# LF_Sensor_Board.net
KiCad netlist of a schematic drawn in Altium Designer
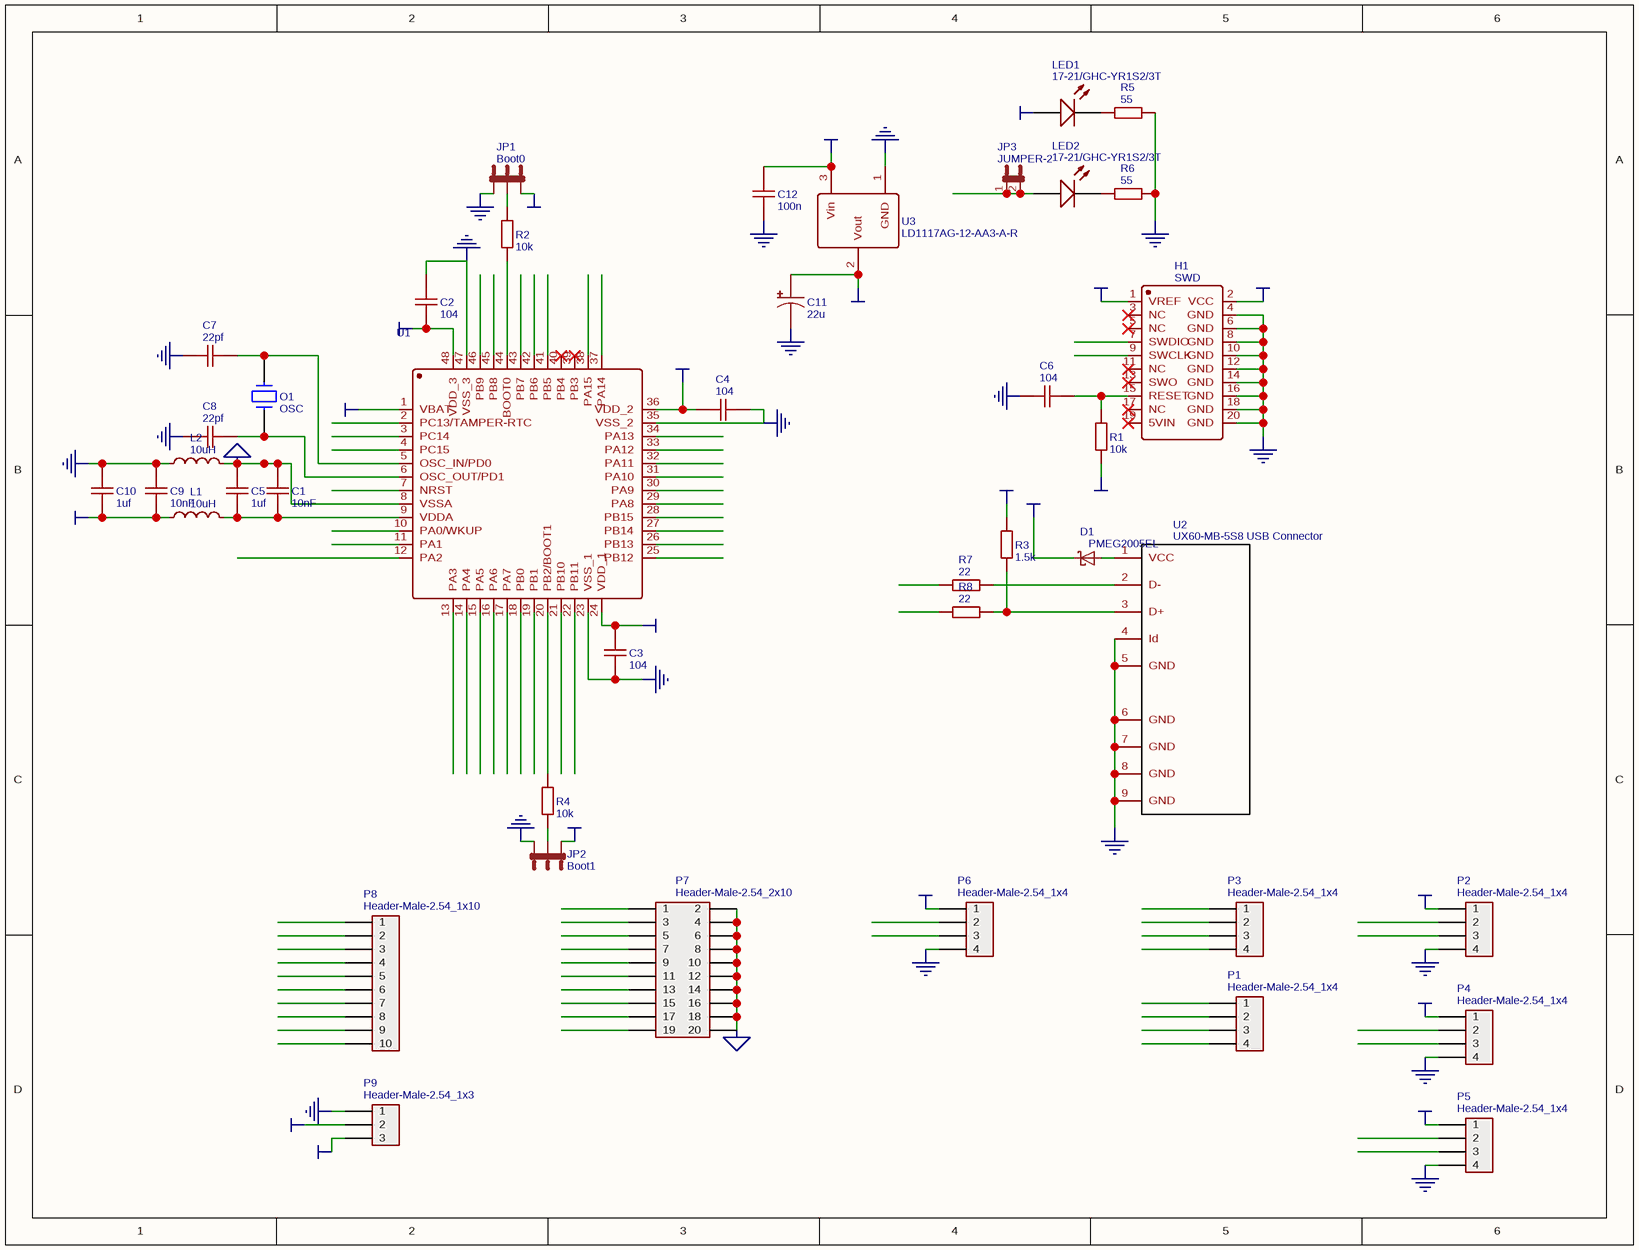
[diagram p0: LF_Sensor_Board.schdoc]

(export (version "E")
  (design (tool "Eeschema 10.0.6"))
  (components
    (comp (ref "C1")
      (value "10nF")
      (fields (field (name "BOM_MANUFACTURER PART") "?"))
      (libsource (lib "altium-import") (part "root_1_10nF_"))
    )
    (comp (ref "C2")
      (value "104")
      (fields (field (name "BOM_MANUFACTURER PART") "?"))
      (libsource (lib "altium-import") (part "root_1_104_"))
    )
    (comp (ref "C3")
      (value "104")
      (fields (field (name "BOM_MANUFACTURER PART") "?"))
      (libsource (lib "altium-import") (part "root_1_104_"))
    )
    (comp (ref "C4")
      (value "104")
      (fields (field (name "BOM_MANUFACTURER PART") "?"))
      (libsource (lib "altium-import") (part "root_0_104_"))
    )
    (comp (ref "C5")
      (value "1uf")
      (fields (field (name "BOM_MANUFACTURER PART") "?"))
      (libsource (lib "altium-import") (part "root_1_1uf_"))
    )
    (comp (ref "C6")
      (value "104")
      (fields (field (name "BOM_MANUFACTURER PART") "?"))
      (libsource (lib "altium-import") (part "root_2_104_"))
    )
    (comp (ref "C7")
      (value "22pf")
      (fields (field (name "BOM_MANUFACTURER PART") "?"))
      (libsource (lib "altium-import") (part "root_0_22pf_"))
    )
    (comp (ref "C8")
      (value "22pf")
      (fields (field (name "BOM_MANUFACTURER PART") "?"))
      (libsource (lib "altium-import") (part "root_0_22pf_"))
    )
    (comp (ref "C9")
      (value "10nF")
      (fields (field (name "BOM_MANUFACTURER PART") "?"))
      (libsource (lib "altium-import") (part "root_1_10nF_"))
    )
    (comp (ref "C10")
      (value "1uf")
      (fields (field (name "BOM_MANUFACTURER PART") "?"))
      (libsource (lib "altium-import") (part "root_1_1uf_"))
    )
    (comp (ref "C11")
      (value "22u")
      (fields (field (name "BOM_MANUFACTURER PART") "?"))
      (libsource (lib "altium-import") (part "root_0_22u_"))
    )
    (comp (ref "C12")
      (value "100n")
      (fields (field (name "BOM_MANUFACTURER PART") "?"))
      (libsource (lib "altium-import") (part "root_1_100n_"))
    )
    (comp (ref "D1")
      (value "PMEG2005EL")
      (fields (field (name "BOM_MANUFACTURER PART") "?"))
      (libsource (lib "altium-import") (part "root_0_PMEG2005EL_"))
    )
    (comp (ref "H1")
      (value "SWD")
      (fields (field (name "BOM_MANUFACTURER PART") "?"))
      (libsource (lib "altium-import") (part "root_0_SWD_"))
    )
    (comp (ref "JP1")
      (value "Boot0")
      (fields (field (name "BOM_MANUFACTURER PART") "?") (field (name "CONTRIBUTOR") "SparkFun"))
      (libsource (lib "altium-import") (part "root_0_Boot0_"))
    )
    (comp (ref "JP2")
      (value "Boot1")
      (fields (field (name "BOM_MANUFACTURER PART") "?") (field (name "CONTRIBUTOR") "SparkFun"))
      (libsource (lib "altium-import") (part "root_0_Boot1_"))
    )
    (comp (ref "JP3")
      (value "JUMPER-2")
      (fields (field (name "BOM_MANUFACTURER PART") "?") (field (name "CONTRIBUTOR") "SparkFun"))
      (libsource (lib "altium-import") (part "root_0_JUMPER-2_"))
    )
    (comp (ref "L1")
      (value "10uH")
      (fields (field (name "BOM_MANUFACTURER PART") "?"))
      (libsource (lib "altium-import") (part "root_0_10uH_"))
    )
    (comp (ref "L2")
      (value "10uH")
      (fields (field (name "BOM_MANUFACTURER PART") "?"))
      (libsource (lib "altium-import") (part "root_0_10uH_"))
    )
    (comp (ref "LED1")
      (value "17-21/GHC-YR1S2/3T")
      (fields (field (name "BOM_SUPPLIER PART") "E73546"))
      (libsource (lib "altium-import") (part "root_0_17-21/GHC-YR1S2/3T_"))
    )
    (comp (ref "LED2")
      (value "17-21/GHC-YR1S2/3T")
      (fields (field (name "BOM_SUPPLIER PART") "E73546"))
      (libsource (lib "altium-import") (part "root_0_17-21/GHC-YR1S2/3T_"))
    )
    (comp (ref "O1")
      (value "OSC")
      (description "晶振")
      (fields (field (name "BOM_MANUFACTURER PART") "?"))
      (libsource (lib "altium-import") (part "root_0_OSC_"))
    )
    (comp (ref "P1")
      (value "Header-Male-2.54_1x4")
      (fields (field (name "BOM_SUPPLIER PART") "E59481"))
      (libsource (lib "altium-import") (part "root_0_Header-Male-2.54_1x4_"))
    )
    (comp (ref "P2")
      (value "Header-Male-2.54_1x4")
      (fields (field (name "BOM_SUPPLIER PART") "E59481"))
      (libsource (lib "altium-import") (part "root_0_Header-Male-2.54_1x4_"))
    )
    (comp (ref "P3")
      (value "Header-Male-2.54_1x4")
      (fields (field (name "BOM_SUPPLIER PART") "E59481"))
      (libsource (lib "altium-import") (part "root_0_Header-Male-2.54_1x4_"))
    )
    (comp (ref "P4")
      (value "Header-Male-2.54_1x4")
      (fields (field (name "BOM_SUPPLIER PART") "E59481"))
      (libsource (lib "altium-import") (part "root_0_Header-Male-2.54_1x4_"))
    )
    (comp (ref "P5")
      (value "Header-Male-2.54_1x4")
      (fields (field (name "BOM_SUPPLIER PART") "E59481"))
      (libsource (lib "altium-import") (part "root_0_Header-Male-2.54_1x4_"))
    )
    (comp (ref "P6")
      (value "Header-Male-2.54_1x4")
      (fields (field (name "BOM_SUPPLIER PART") "E59481"))
      (libsource (lib "altium-import") (part "root_0_Header-Male-2.54_1x4_"))
    )
    (comp (ref "P7")
      (value "Header-Male-2.54_2x10")
      (fields (field (name "BOM_SUPPLIER PART") "E62032"))
      (libsource (lib "altium-import") (part "root_0_Header-Male-2.54_2x10_"))
    )
    (comp (ref "P8")
      (value "Header-Male-2.54_1x10")
      (fields (field (name "BOM_SUPPLIER PART") "E57369"))
      (libsource (lib "altium-import") (part "root_0_Header-Male-2.54_1x10_"))
    )
    (comp (ref "P9")
      (value "Header-Male-2.54_1x3")
      (fields (field (name "BOM_SUPPLIER PART") "E49257"))
      (libsource (lib "altium-import") (part "root_0_Header-Male-2.54_1x3_"))
    )
    (comp (ref "R1")
      (value "10k")
      (fields (field (name "BOM_MANUFACTURER PART") "?"))
      (libsource (lib "altium-import") (part "root_1_10k_"))
    )
    (comp (ref "R2")
      (value "10k")
      (fields (field (name "BOM_MANUFACTURER PART") "?"))
      (libsource (lib "altium-import") (part "root_1_10k_"))
    )
    (comp (ref "R3")
      (value "1.5k")
      (fields (field (name "BOM_MANUFACTURER PART") "?"))
      (libsource (lib "altium-import") (part "root_1_1.5k_"))
    )
    (comp (ref "R4")
      (value "10k")
      (fields (field (name "BOM_MANUFACTURER PART") "?"))
      (libsource (lib "") (part "root_1_10k__1"))
    )
    (comp (ref "R5")
      (value "55")
      (fields (field (name "BOM_MANUFACTURER PART") "?"))
      (libsource (lib "altium-import") (part "root_0_55_"))
    )
    (comp (ref "R6")
      (value "55")
      (fields (field (name "BOM_MANUFACTURER PART") "?"))
      (libsource (lib "altium-import") (part "root_0_55_"))
    )
    (comp (ref "R7")
      (value "22")
      (fields (field (name "BOM_MANUFACTURER PART") "?"))
      (libsource (lib "altium-import") (part "root_0_22_"))
    )
    (comp (ref "R8")
      (value "22")
      (fields (field (name "BOM_MANUFACTURER PART") "?"))
      (libsource (lib "altium-import") (part "root_0_22_"))
    )
    (comp (ref "U1")
      (value "STM32F103C8T6")
      (fields (field (name "BOM_MANUFACTURER PART") "?"))
      (libsource (lib "altium-import") (part "root_0_STM32F103C8T6_"))
    )
    (comp (ref "U2")
      (value "UX60-MB-5S8 USB Connector")
      (fields (field (name "BOM_MANUFACTURER PART") "?") (field (name "CONTRIBUTOR") "fbruckm"))
      (libsource (lib "altium-import") (part "root_2_UX60-MB-5S8 USB Connector_"))
    )
    (comp (ref "U3")
      (value "LD1117AG-12-AA3-A-R")
      (fields (field (name "BOM_SUPPLIER PART") "E75486"))
      (libsource (lib "altium-import") (part "root_1_LD1117AG-12-AA3-A-R_"))
    )
  )
  (nets
    (net (code "1") (name "<NO NET>") (class "Default")
      (node (ref "C1") (pin "2") (pinfunction "2_2") (pintype "passive"))
      (node (ref "C10") (pin "1") (pinfunction "1_1") (pintype "passive"))
      (node (ref "C10") (pin "2") (pinfunction "2_2") (pintype "passive"))
      (node (ref "C11") (pin "1") (pinfunction "1_1") (pintype "passive"))
      (node (ref "C11") (pin "2") (pinfunction "2_2") (pintype "passive"))
      (node (ref "C12") (pin "1") (pinfunction "1_1") (pintype "passive"))
      (node (ref "C12") (pin "2") (pinfunction "2_2") (pintype "passive"))
      (node (ref "C2") (pin "1") (pinfunction "1_1") (pintype "passive"))
      (node (ref "C2") (pin "2") (pinfunction "2_2") (pintype "passive"))
      (node (ref "C3") (pin "1") (pinfunction "1_1") (pintype "passive"))
      (node (ref "C3") (pin "2") (pinfunction "2_2") (pintype "passive"))
      (node (ref "C4") (pin "1") (pinfunction "1_1") (pintype "passive"))
      (node (ref "C4") (pin "2") (pinfunction "2_2") (pintype "passive"))
      (node (ref "C5") (pin "2") (pinfunction "2_2") (pintype "passive"))
      (node (ref "C6") (pin "2") (pinfunction "2_2") (pintype "passive"))
      (node (ref "C7") (pin "1") (pinfunction "1_1") (pintype "passive"))
      (node (ref "C8") (pin "1") (pinfunction "1_1") (pintype "passive"))
      (node (ref "C9") (pin "1") (pinfunction "1_1") (pintype "passive"))
      (node (ref "C9") (pin "2") (pinfunction "2_2") (pintype "passive"))
      (node (ref "D1") (pin "1") (pinfunction "K_1") (pintype "passive"))
      (node (ref "H1") (pin "1") (pinfunction "VREF_1") (pintype "passive"))
      (node (ref "H1") (pin "10") (pinfunction "GND_10") (pintype "passive"))
      (node (ref "H1") (pin "12") (pinfunction "GND_12") (pintype "passive"))
      (node (ref "H1") (pin "14") (pinfunction "GND_14") (pintype "passive"))
      (node (ref "H1") (pin "16") (pinfunction "GND_16") (pintype "passive"))
      (node (ref "H1") (pin "18") (pinfunction "GND_18") (pintype "passive"))
      (node (ref "H1") (pin "2") (pinfunction "VCC_2") (pintype "passive"))
      (node (ref "H1") (pin "20") (pinfunction "GND_20") (pintype "passive"))
      (node (ref "H1") (pin "4") (pinfunction "GND_4") (pintype "passive"))
      (node (ref "H1") (pin "6") (pinfunction "GND_6") (pintype "passive"))
      (node (ref "H1") (pin "8") (pinfunction "GND_8") (pintype "passive"))
      (node (ref "JP1") (pin "1") (pinfunction "1_1") (pintype "passive"))
      (node (ref "JP1") (pin "3") (pinfunction "3_3") (pintype "passive"))
      (node (ref "JP2") (pin "1") (pinfunction "1_1") (pintype "passive"))
      (node (ref "JP2") (pin "3") (pinfunction "3_3") (pintype "passive"))
      (node (ref "L1") (pin "1") (pinfunction "1_1") (pintype "passive"))
      (node (ref "L2") (pin "1") (pinfunction "1_1") (pintype "passive"))
      (node (ref "L2") (pin "2") (pinfunction "2_2") (pintype "passive"))
      (node (ref "LED1") (pin "1") (pinfunction "A_1") (pintype "passive"))
      (node (ref "P2") (pin "1") (pinfunction "1_1") (pintype "passive"))
      (node (ref "P2") (pin "4") (pinfunction "4_4") (pintype "passive"))
      (node (ref "P4") (pin "1") (pinfunction "1_1") (pintype "passive"))
      (node (ref "P4") (pin "4") (pinfunction "4_4") (pintype "passive"))
      (node (ref "P5") (pin "1") (pinfunction "1_1") (pintype "passive"))
      (node (ref "P5") (pin "4") (pinfunction "4_4") (pintype "passive"))
      (node (ref "P6") (pin "1") (pinfunction "1_1") (pintype "passive"))
      (node (ref "P6") (pin "4") (pinfunction "4_4") (pintype "passive"))
      (node (ref "P7") (pin "10") (pinfunction "10_10") (pintype "passive"))
      (node (ref "P7") (pin "12") (pinfunction "12_12") (pintype "passive"))
      (node (ref "P7") (pin "14") (pinfunction "14_14") (pintype "passive"))
      (node (ref "P7") (pin "16") (pinfunction "16_16") (pintype "passive"))
      (node (ref "P7") (pin "18") (pinfunction "18_18") (pintype "passive"))
      (node (ref "P7") (pin "2") (pinfunction "2_2") (pintype "passive"))
      (node (ref "P7") (pin "20") (pinfunction "20_20") (pintype "passive"))
      (node (ref "P7") (pin "4") (pinfunction "4_4") (pintype "passive"))
      (node (ref "P7") (pin "6") (pinfunction "6_6") (pintype "passive"))
      (node (ref "P7") (pin "8") (pinfunction "8_8") (pintype "passive"))
      (node (ref "P9") (pin "1") (pinfunction "1_1") (pintype "passive"))
      (node (ref "P9") (pin "2") (pinfunction "2_2") (pintype "passive"))
      (node (ref "P9") (pin "3") (pinfunction "3_3") (pintype "passive"))
      (node (ref "R1") (pin "1") (pinfunction "1_1") (pintype "passive"))
      (node (ref "R3") (pin "2") (pinfunction "2_2") (pintype "passive"))
      (node (ref "R5") (pin "2") (pinfunction "2_2") (pintype "passive"))
      (node (ref "R6") (pin "2") (pinfunction "2_2") (pintype "passive"))
      (node (ref "U1") (pin "1") (pinfunction "VBAT_1") (pintype "passive"))
      (node (ref "U1") (pin "23") (pinfunction "VSS_1_23") (pintype "passive"))
      (node (ref "U1") (pin "24") (pinfunction "VDD_1_24") (pintype "passive"))
      (node (ref "U1") (pin "35") (pinfunction "VSS_2_35") (pintype "passive"))
      (node (ref "U1") (pin "36") (pinfunction "VDD_2_36") (pintype "passive"))
      (node (ref "U1") (pin "47") (pinfunction "VSS_3_47") (pintype "passive"))
      (node (ref "U1") (pin "48") (pinfunction "VDD_3_48") (pintype "passive"))
      (node (ref "U1") (pin "8") (pinfunction "VSSA_8") (pintype "passive"))
      (node (ref "U2") (pin "4") (pinfunction "Id_4") (pintype "passive"))
      (node (ref "U2") (pin "5") (pinfunction "GND_5") (pintype "passive"))
      (node (ref "U2") (pin "6") (pinfunction "GND_6") (pintype "passive"))
      (node (ref "U2") (pin "7") (pinfunction "GND_7") (pintype "passive"))
      (node (ref "U2") (pin "8") (pinfunction "GND_8") (pintype "passive"))
      (node (ref "U2") (pin "9") (pinfunction "GND_9") (pintype "passive"))
      (node (ref "U3") (pin "1") (pinfunction "GND_1") (pintype "passive"))
      (node (ref "U3") (pin "2") (pinfunction "Vout_2") (pintype "passive"))
      (node (ref "U3") (pin "3") (pinfunction "Vin_3") (pintype "passive"))
    )
    (net (code "2") (name "Net-(D1-A)") (class "Default")
      (node (ref "D1") (pin "2") (pinfunction "A_2") (pintype "passive"))
      (node (ref "U2") (pin "1") (pinfunction "VCC_1") (pintype "passive"))
    )
    (net (code "3") (name "Net-(H1-RESET)") (class "Default")
      (node (ref "C6") (pin "1") (pinfunction "1_1") (pintype "passive"))
      (node (ref "H1") (pin "15") (pinfunction "RESET_15") (pintype "passive"))
      (node (ref "R1") (pin "2") (pinfunction "2_2") (pintype "passive"))
    )
    (net (code "4") (name "Net-(JP1-Pad2)") (class "Default")
      (node (ref "JP1") (pin "2") (pinfunction "2_2") (pintype "passive"))
      (node (ref "R2") (pin "2") (pinfunction "2_2") (pintype "passive"))
    )
    (net (code "5") (name "Net-(JP2-Pad2)") (class "Default")
      (node (ref "JP2") (pin "2") (pinfunction "2_2") (pintype "passive"))
      (node (ref "R4") (pin "2") (pinfunction "2_2") (pintype "passive"))
    )
    (net (code "6") (name "Net-(LED1-C)") (class "Default")
      (node (ref "LED1") (pin "2") (pinfunction "C_2") (pintype "passive"))
      (node (ref "R5") (pin "1") (pinfunction "1_1") (pintype "passive"))
    )
    (net (code "7") (name "Net-(LED2-A)") (class "Default")
      (node (ref "JP3") (pin "1") (pinfunction "1_1") (pintype "passive"))
      (node (ref "JP3") (pin "2") (pinfunction "2_2") (pintype "passive"))
      (node (ref "LED2") (pin "1") (pinfunction "A_1") (pintype "passive"))
    )
    (net (code "8") (name "Net-(LED2-C)") (class "Default")
      (node (ref "LED2") (pin "2") (pinfunction "C_2") (pintype "passive"))
      (node (ref "R6") (pin "1") (pinfunction "1_1") (pintype "passive"))
    )
    (net (code "9") (name "Net-(U1-BOOT0)") (class "Default")
      (node (ref "R2") (pin "1") (pinfunction "1_1") (pintype "passive"))
      (node (ref "U1") (pin "44") (pinfunction "BOOT0_44") (pintype "passive"))
    )
    (net (code "10") (name "Net-(U1-OSC_IN{slash}PD0)") (class "Default")
      (node (ref "C7") (pin "2") (pinfunction "2_2") (pintype "passive"))
      (node (ref "O1") (pin "2") (pinfunction "2_2") (pintype "passive"))
      (node (ref "U1") (pin "5") (pinfunction "OSC_IN/PD0_5") (pintype "passive"))
    )
    (net (code "11") (name "Net-(U1-OSC_OUT{slash}PD1)") (class "Default")
      (node (ref "C8") (pin "2") (pinfunction "2_2") (pintype "passive"))
      (node (ref "O1") (pin "1") (pinfunction "1_1") (pintype "passive"))
      (node (ref "U1") (pin "6") (pinfunction "OSC_OUT/PD1_6") (pintype "passive"))
    )
    (net (code "12") (name "Net-(U1-PB2{slash}BOOT1)") (class "Default")
      (node (ref "R4") (pin "1") (pinfunction "1_1") (pintype "passive"))
      (node (ref "U1") (pin "20") (pinfunction "PB2/BOOT1_20") (pintype "passive"))
    )
    (net (code "13") (name "Net-(U1-VDDA)") (class "Default")
      (node (ref "C1") (pin "1") (pinfunction "1_1") (pintype "passive"))
      (node (ref "C5") (pin "1") (pinfunction "1_1") (pintype "passive"))
      (node (ref "L1") (pin "2") (pinfunction "2_2") (pintype "passive"))
      (node (ref "U1") (pin "9") (pinfunction "VDDA_9") (pintype "passive"))
    )
    (net (code "14") (name "Net-(U2-D+)") (class "Default")
      (node (ref "R3") (pin "1") (pinfunction "1_1") (pintype "passive"))
      (node (ref "R8") (pin "2") (pinfunction "2_2") (pintype "passive"))
      (node (ref "U2") (pin "3") (pinfunction "D+_3") (pintype "passive"))
    )
    (net (code "15") (name "Net-(U2-D-)") (class "Default")
      (node (ref "R7") (pin "2") (pinfunction "2_2") (pintype "passive"))
      (node (ref "U2") (pin "2") (pinfunction "D-_2") (pintype "passive"))
    )
    (net (code "16") (name "unconnected-(H1-5VIN-Pad19)") (class "Default")
      (node (ref "H1") (pin "19") (pinfunction "5VIN_19") (pintype "passive+no_connect"))
    )
    (net (code "17") (name "unconnected-(H1-NC-Pad3)") (class "Default")
      (node (ref "H1") (pin "3") (pinfunction "NC_3") (pintype "passive+no_connect"))
    )
    (net (code "18") (name "unconnected-(H1-NC-Pad5)") (class "Default")
      (node (ref "H1") (pin "5") (pinfunction "NC_5") (pintype "passive+no_connect"))
    )
    (net (code "19") (name "unconnected-(H1-NC-Pad11)") (class "Default")
      (node (ref "H1") (pin "11") (pinfunction "NC_11") (pintype "passive+no_connect"))
    )
    (net (code "20") (name "unconnected-(H1-NC-Pad17)") (class "Default")
      (node (ref "H1") (pin "17") (pinfunction "NC_17") (pintype "passive+no_connect"))
    )
    (net (code "21") (name "unconnected-(H1-SWCLK-Pad9)") (class "Default")
      (node (ref "H1") (pin "9") (pinfunction "SWCLK_9") (pintype "passive"))
    )
    (net (code "22") (name "unconnected-(H1-SWDIO-Pad7)") (class "Default")
      (node (ref "H1") (pin "7") (pinfunction "SWDIO_7") (pintype "passive"))
    )
    (net (code "23") (name "unconnected-(H1-SWO-Pad13)") (class "Default")
      (node (ref "H1") (pin "13") (pinfunction "SWO_13") (pintype "passive+no_connect"))
    )
    (net (code "24") (name "unconnected-(P1-Pad1)") (class "Default")
      (node (ref "P1") (pin "1") (pinfunction "1_1") (pintype "passive"))
    )
    (net (code "25") (name "unconnected-(P1-Pad2)") (class "Default")
      (node (ref "P1") (pin "2") (pinfunction "2_2") (pintype "passive"))
    )
    (net (code "26") (name "unconnected-(P1-Pad3)") (class "Default")
      (node (ref "P1") (pin "3") (pinfunction "3_3") (pintype "passive"))
    )
    (net (code "27") (name "unconnected-(P1-Pad4)") (class "Default")
      (node (ref "P1") (pin "4") (pinfunction "4_4") (pintype "passive"))
    )
    (net (code "28") (name "unconnected-(P2-Pad2)") (class "Default")
      (node (ref "P2") (pin "2") (pinfunction "2_2") (pintype "passive"))
    )
    (net (code "29") (name "unconnected-(P2-Pad3)") (class "Default")
      (node (ref "P2") (pin "3") (pinfunction "3_3") (pintype "passive"))
    )
    (net (code "30") (name "unconnected-(P3-Pad1)") (class "Default")
      (node (ref "P3") (pin "1") (pinfunction "1_1") (pintype "passive"))
    )
    (net (code "31") (name "unconnected-(P3-Pad2)") (class "Default")
      (node (ref "P3") (pin "2") (pinfunction "2_2") (pintype "passive"))
    )
    (net (code "32") (name "unconnected-(P3-Pad3)") (class "Default")
      (node (ref "P3") (pin "3") (pinfunction "3_3") (pintype "passive"))
    )
    (net (code "33") (name "unconnected-(P3-Pad4)") (class "Default")
      (node (ref "P3") (pin "4") (pinfunction "4_4") (pintype "passive"))
    )
    (net (code "34") (name "unconnected-(P4-Pad2)") (class "Default")
      (node (ref "P4") (pin "2") (pinfunction "2_2") (pintype "passive"))
    )
    (net (code "35") (name "unconnected-(P4-Pad3)") (class "Default")
      (node (ref "P4") (pin "3") (pinfunction "3_3") (pintype "passive"))
    )
    (net (code "36") (name "unconnected-(P5-Pad2)") (class "Default")
      (node (ref "P5") (pin "2") (pinfunction "2_2") (pintype "passive"))
    )
    (net (code "37") (name "unconnected-(P5-Pad3)") (class "Default")
      (node (ref "P5") (pin "3") (pinfunction "3_3") (pintype "passive"))
    )
    (net (code "38") (name "unconnected-(P6-Pad2)") (class "Default")
      (node (ref "P6") (pin "2") (pinfunction "2_2") (pintype "passive"))
    )
    (net (code "39") (name "unconnected-(P6-Pad3)") (class "Default")
      (node (ref "P6") (pin "3") (pinfunction "3_3") (pintype "passive"))
    )
    (net (code "40") (name "unconnected-(P7-Pad1)") (class "Default")
      (node (ref "P7") (pin "1") (pinfunction "1_1") (pintype "passive"))
    )
    (net (code "41") (name "unconnected-(P7-Pad3)") (class "Default")
      (node (ref "P7") (pin "3") (pinfunction "3_3") (pintype "passive"))
    )
    (net (code "42") (name "unconnected-(P7-Pad5)") (class "Default")
      (node (ref "P7") (pin "5") (pinfunction "5_5") (pintype "passive"))
    )
    (net (code "43") (name "unconnected-(P7-Pad7)") (class "Default")
      (node (ref "P7") (pin "7") (pinfunction "7_7") (pintype "passive"))
    )
    (net (code "44") (name "unconnected-(P7-Pad9)") (class "Default")
      (node (ref "P7") (pin "9") (pinfunction "9_9") (pintype "passive"))
    )
    (net (code "45") (name "unconnected-(P7-Pad11)") (class "Default")
      (node (ref "P7") (pin "11") (pinfunction "11_11") (pintype "passive"))
    )
    (net (code "46") (name "unconnected-(P7-Pad13)") (class "Default")
      (node (ref "P7") (pin "13") (pinfunction "13_13") (pintype "passive"))
    )
    (net (code "47") (name "unconnected-(P7-Pad15)") (class "Default")
      (node (ref "P7") (pin "15") (pinfunction "15_15") (pintype "passive"))
    )
    (net (code "48") (name "unconnected-(P7-Pad17)") (class "Default")
      (node (ref "P7") (pin "17") (pinfunction "17_17") (pintype "passive"))
    )
    (net (code "49") (name "unconnected-(P7-Pad19)") (class "Default")
      (node (ref "P7") (pin "19") (pinfunction "19_19") (pintype "passive"))
    )
    (net (code "50") (name "unconnected-(P8-Pad1)") (class "Default")
      (node (ref "P8") (pin "1") (pinfunction "1_1") (pintype "passive"))
    )
    (net (code "51") (name "unconnected-(P8-Pad2)") (class "Default")
      (node (ref "P8") (pin "2") (pinfunction "2_2") (pintype "passive"))
    )
    (net (code "52") (name "unconnected-(P8-Pad3)") (class "Default")
      (node (ref "P8") (pin "3") (pinfunction "3_3") (pintype "passive"))
    )
    (net (code "53") (name "unconnected-(P8-Pad4)") (class "Default")
      (node (ref "P8") (pin "4") (pinfunction "4_4") (pintype "passive"))
    )
    (net (code "54") (name "unconnected-(P8-Pad5)") (class "Default")
      (node (ref "P8") (pin "5") (pinfunction "5_5") (pintype "passive"))
    )
    (net (code "55") (name "unconnected-(P8-Pad6)") (class "Default")
      (node (ref "P8") (pin "6") (pinfunction "6_6") (pintype "passive"))
    )
    (net (code "56") (name "unconnected-(P8-Pad7)") (class "Default")
      (node (ref "P8") (pin "7") (pinfunction "7_7") (pintype "passive"))
    )
    (net (code "57") (name "unconnected-(P8-Pad8)") (class "Default")
      (node (ref "P8") (pin "8") (pinfunction "8_8") (pintype "passive"))
    )
    (net (code "58") (name "unconnected-(P8-Pad9)") (class "Default")
      (node (ref "P8") (pin "9") (pinfunction "9_9") (pintype "passive"))
    )
    (net (code "59") (name "unconnected-(P8-Pad10)") (class "Default")
      (node (ref "P8") (pin "10") (pinfunction "10_10") (pintype "passive"))
    )
    (net (code "60") (name "unconnected-(R7-Pad1)") (class "Default")
      (node (ref "R7") (pin "1") (pinfunction "1_1") (pintype "passive"))
    )
    (net (code "61") (name "unconnected-(R8-Pad1)") (class "Default")
      (node (ref "R8") (pin "1") (pinfunction "1_1") (pintype "passive"))
    )
    (net (code "62") (name "unconnected-(U1-NRST-Pad7)") (class "Default")
      (node (ref "U1") (pin "7") (pinfunction "NRST_7") (pintype "passive"))
    )
    (net (code "63") (name "unconnected-(U1-PA0{slash}WKUP-Pad10)") (class "Default")
      (node (ref "U1") (pin "10") (pinfunction "PA0/WKUP_10") (pintype "passive"))
    )
    (net (code "64") (name "unconnected-(U1-PA1-Pad11)") (class "Default")
      (node (ref "U1") (pin "11") (pinfunction "PA1_11") (pintype "passive"))
    )
    (net (code "65") (name "unconnected-(U1-PA2-Pad12)") (class "Default")
      (node (ref "U1") (pin "12") (pinfunction "PA2_12") (pintype "passive"))
    )
    (net (code "66") (name "unconnected-(U1-PA3-Pad13)") (class "Default")
      (node (ref "U1") (pin "13") (pinfunction "PA3_13") (pintype "passive"))
    )
    (net (code "67") (name "unconnected-(U1-PA4-Pad14)") (class "Default")
      (node (ref "U1") (pin "14") (pinfunction "PA4_14") (pintype "passive"))
    )
    (net (code "68") (name "unconnected-(U1-PA5-Pad15)") (class "Default")
      (node (ref "U1") (pin "15") (pinfunction "PA5_15") (pintype "passive"))
    )
    (net (code "69") (name "unconnected-(U1-PA6-Pad16)") (class "Default")
      (node (ref "U1") (pin "16") (pinfunction "PA6_16") (pintype "passive"))
    )
    (net (code "70") (name "unconnected-(U1-PA7-Pad17)") (class "Default")
      (node (ref "U1") (pin "17") (pinfunction "PA7_17") (pintype "passive"))
    )
    (net (code "71") (name "unconnected-(U1-PA8-Pad29)") (class "Default")
      (node (ref "U1") (pin "29") (pinfunction "PA8_29") (pintype "passive"))
    )
    (net (code "72") (name "unconnected-(U1-PA9-Pad30)") (class "Default")
      (node (ref "U1") (pin "30") (pinfunction "PA9_30") (pintype "passive"))
    )
    (net (code "73") (name "unconnected-(U1-PA10-Pad31)") (class "Default")
      (node (ref "U1") (pin "31") (pinfunction "PA10_31") (pintype "passive"))
    )
    (net (code "74") (name "unconnected-(U1-PA11-Pad32)") (class "Default")
      (node (ref "U1") (pin "32") (pinfunction "PA11_32") (pintype "passive"))
    )
    (net (code "75") (name "unconnected-(U1-PA12-Pad33)") (class "Default")
      (node (ref "U1") (pin "33") (pinfunction "PA12_33") (pintype "passive"))
    )
    (net (code "76") (name "unconnected-(U1-PA13-Pad34)") (class "Default")
      (node (ref "U1") (pin "34") (pinfunction "PA13_34") (pintype "passive"))
    )
    (net (code "77") (name "unconnected-(U1-PA14-Pad37)") (class "Default")
      (node (ref "U1") (pin "37") (pinfunction "PA14_37") (pintype "passive"))
    )
    (net (code "78") (name "unconnected-(U1-PA15-Pad38)") (class "Default")
      (node (ref "U1") (pin "38") (pinfunction "PA15_38") (pintype "passive"))
    )
    (net (code "79") (name "unconnected-(U1-PB0-Pad18)") (class "Default")
      (node (ref "U1") (pin "18") (pinfunction "PB0_18") (pintype "passive"))
    )
    (net (code "80") (name "unconnected-(U1-PB1-Pad19)") (class "Default")
      (node (ref "U1") (pin "19") (pinfunction "PB1_19") (pintype "passive"))
    )
    (net (code "81") (name "unconnected-(U1-PB3-Pad39)") (class "Default")
      (node (ref "U1") (pin "39") (pinfunction "PB3_39") (pintype "passive+no_connect"))
    )
    (net (code "82") (name "unconnected-(U1-PB4-Pad40)") (class "Default")
      (node (ref "U1") (pin "40") (pinfunction "PB4_40") (pintype "passive+no_connect"))
    )
    (net (code "83") (name "unconnected-(U1-PB5-Pad41)") (class "Default")
      (node (ref "U1") (pin "41") (pinfunction "PB5_41") (pintype "passive"))
    )
    (net (code "84") (name "unconnected-(U1-PB6-Pad42)") (class "Default")
      (node (ref "U1") (pin "42") (pinfunction "PB6_42") (pintype "passive"))
    )
    (net (code "85") (name "unconnected-(U1-PB7-Pad43)") (class "Default")
      (node (ref "U1") (pin "43") (pinfunction "PB7_43") (pintype "passive"))
    )
    (net (code "86") (name "unconnected-(U1-PB8-Pad45)") (class "Default")
      (node (ref "U1") (pin "45") (pinfunction "PB8_45") (pintype "passive"))
    )
    (net (code "87") (name "unconnected-(U1-PB9-Pad46)") (class "Default")
      (node (ref "U1") (pin "46") (pinfunction "PB9_46") (pintype "passive"))
    )
    (net (code "88") (name "unconnected-(U1-PB10-Pad21)") (class "Default")
      (node (ref "U1") (pin "21") (pinfunction "PB10_21") (pintype "passive"))
    )
    (net (code "89") (name "unconnected-(U1-PB11-Pad22)") (class "Default")
      (node (ref "U1") (pin "22") (pinfunction "PB11_22") (pintype "passive"))
    )
    (net (code "90") (name "unconnected-(U1-PB12-Pad25)") (class "Default")
      (node (ref "U1") (pin "25") (pinfunction "PB12_25") (pintype "passive"))
    )
    (net (code "91") (name "unconnected-(U1-PB13-Pad26)") (class "Default")
      (node (ref "U1") (pin "26") (pinfunction "PB13_26") (pintype "passive"))
    )
    (net (code "92") (name "unconnected-(U1-PB14-Pad27)") (class "Default")
      (node (ref "U1") (pin "27") (pinfunction "PB14_27") (pintype "passive"))
    )
    (net (code "93") (name "unconnected-(U1-PB15-Pad28)") (class "Default")
      (node (ref "U1") (pin "28") (pinfunction "PB15_28") (pintype "passive"))
    )
    (net (code "94") (name "unconnected-(U1-PC13{slash}TAMPER-RTC-Pad2)") (class "Default")
      (node (ref "U1") (pin "2") (pinfunction "PC13/TAMPER-RTC_2") (pintype "passive"))
    )
    (net (code "95") (name "unconnected-(U1-PC14-Pad3)") (class "Default")
      (node (ref "U1") (pin "3") (pinfunction "PC14_3") (pintype "passive"))
    )
    (net (code "96") (name "unconnected-(U1-PC15-Pad4)") (class "Default")
      (node (ref "U1") (pin "4") (pinfunction "PC15_4") (pintype "passive"))
    )
  )
)
